# gsmwattsmonitor.net
KiCad netlist of a schematic drawn in EAGLE
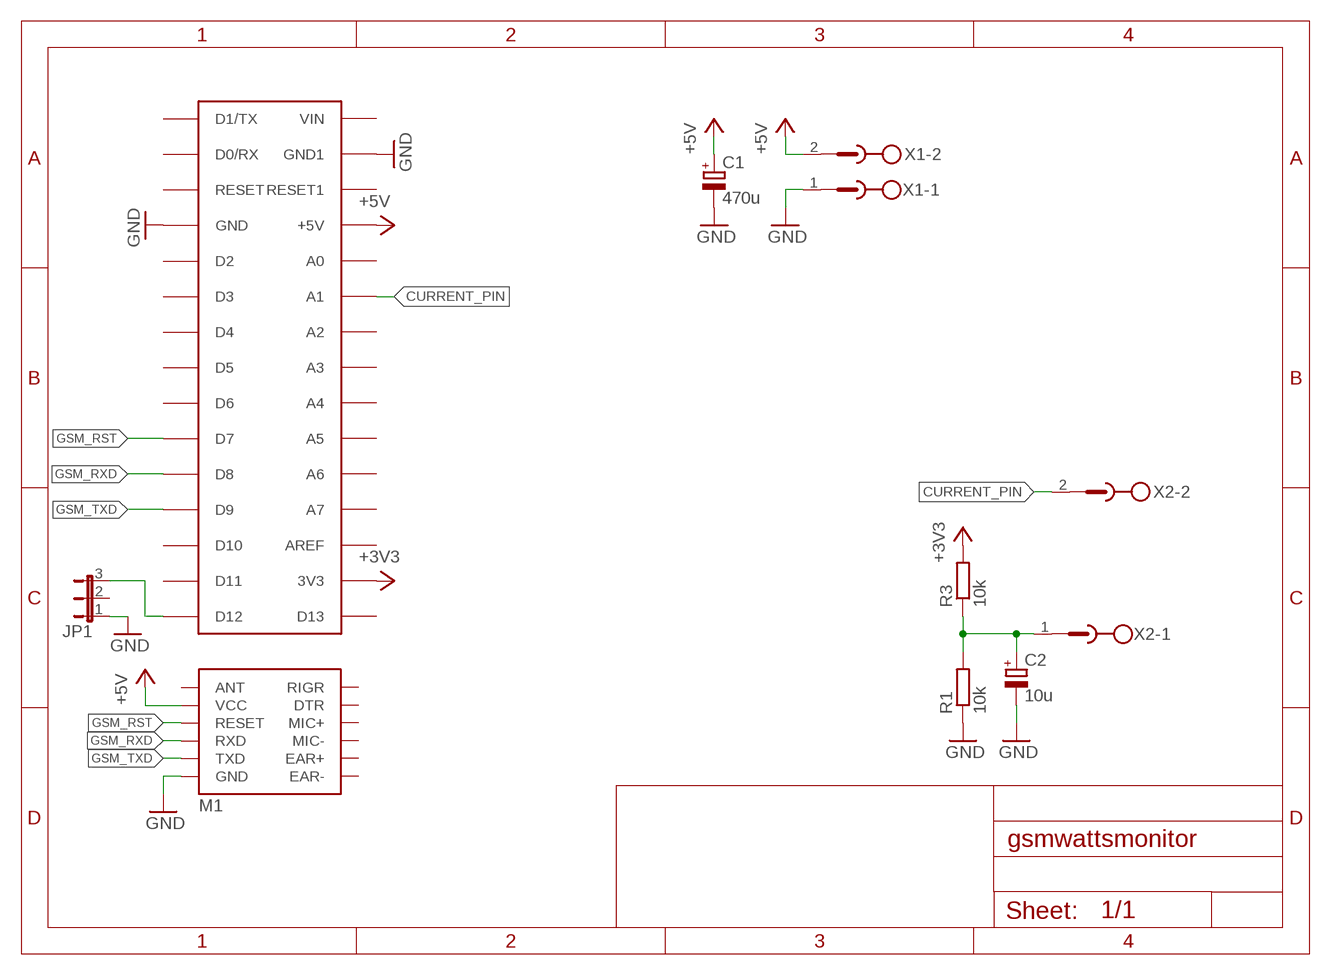
[diagram p0: schematic, sheet 1]

(export (version "E")
  (design (tool "Eeschema 10.0.6"))
  (components
    (comp (ref "C1")
      (value "470u")
      (footprint "eagle-import:E2,5-6")
      (libsource (lib "eagle-import") (part "CPOL-EUE2.5-6"))
    )
    (comp (ref "C2")
      (value "10u")
      (footprint "eagle-import:E2-4")
      (libsource (lib "eagle-import") (part "CPOL-EUE2-4"))
    )
    (comp (ref "JP1")
      (value "JP2E")
      (footprint "eagle-import:JP2")
      (libsource (lib "eagle-import") (part "JP2E"))
    )
    (comp (ref "M1")
      (value "SIM800L")
      (footprint "eagle-import:SIM800L")
      (libsource (lib "eagle-import") (part "SIM800L"))
    )
    (comp (ref "R1")
      (value "10k")
      (footprint "eagle-import:0204_7")
      (libsource (lib "eagle-import") (part "R-EU_0204/7"))
    )
    (comp (ref "R3")
      (value "10k")
      (footprint "eagle-import:0204_7")
      (libsource (lib "eagle-import") (part "R-EU_0204/7"))
    )
    (comp (ref "U$1")
      (value "ARDUINONANO")
      (footprint "eagle-import:PDIP-32")
      (libsource (lib "eagle-import") (part "ARDUINONANO"))
    )
    (comp (ref "X1")
      (value "MSTBV2")
      (footprint "eagle-import:MSTBV2")
      (libsource (lib "eagle-import") (part "MSTBV2"))
    )
    (comp (ref "X2")
      (value "MSTBV2")
      (footprint "eagle-import:MSTBV2")
      (libsource (lib "eagle-import") (part "MSTBV2"))
    )
  )
  (nets
    (net (code "1") (name "+3V3") (class "Default")
      (node (ref "R3") (pin "2") (pinfunction "2_2") (pintype "passive"))
      (node (ref "U$1") (pin "3V3") (pinfunction "3V3_3V3") (pintype "bidirectional"))
    )
    (net (code "2") (name "+5V") (class "Default")
      (node (ref "C1") (pin "+") (pinfunction "+_+") (pintype "passive"))
      (node (ref "M1") (pin "VCC") (pinfunction "VCC_VCC") (pintype "bidirectional"))
      (node (ref "U$1") (pin "+5V") (pinfunction "+5V_+5V") (pintype "bidirectional"))
      (node (ref "X1") (pin "2") (pinfunction "SK_2") (pintype "passive"))
    )
    (net (code "3") (name "CURRENT_PIN") (class "Default")
      (node (ref "U$1") (pin "A1") (pinfunction "A1_A1") (pintype "bidirectional"))
      (node (ref "X2") (pin "2") (pinfunction "SK_2") (pintype "passive"))
    )
    (net (code "4") (name "GND") (class "Default")
      (node (ref "C1") (pin "-") (pinfunction "-_-") (pintype "passive"))
      (node (ref "C2") (pin "-") (pinfunction "-_-") (pintype "passive"))
      (node (ref "JP1") (pin "1") (pinfunction "1_1") (pintype "passive"))
      (node (ref "M1") (pin "GND") (pinfunction "GND_GND") (pintype "bidirectional"))
      (node (ref "R1") (pin "1") (pinfunction "1_1") (pintype "passive"))
      (node (ref "U$1") (pin "GND") (pinfunction "GND_GND") (pintype "bidirectional"))
      (node (ref "U$1") (pin "GND1") (pinfunction "GND1_GND1") (pintype "bidirectional"))
      (node (ref "X1") (pin "1") (pinfunction "SK_1") (pintype "passive"))
    )
    (net (code "5") (name "GSM_RST") (class "Default")
      (node (ref "M1") (pin "RESET") (pinfunction "RESET_RESET") (pintype "bidirectional"))
      (node (ref "U$1") (pin "D7") (pinfunction "D7_D7") (pintype "bidirectional"))
    )
    (net (code "6") (name "GSM_RXD") (class "Default")
      (node (ref "M1") (pin "RXD") (pinfunction "RXD_RXD") (pintype "bidirectional"))
      (node (ref "U$1") (pin "D8") (pinfunction "D8_D8") (pintype "bidirectional"))
    )
    (net (code "7") (name "GSM_TXD") (class "Default")
      (node (ref "M1") (pin "TXD") (pinfunction "TXD_TXD") (pintype "bidirectional"))
      (node (ref "U$1") (pin "D9") (pinfunction "D9_D9") (pintype "bidirectional"))
    )
    (net (code "8") (name "Net-(JP1-Pad3)") (class "Default")
      (node (ref "JP1") (pin "3") (pinfunction "3_3") (pintype "passive"))
      (node (ref "U$1") (pin "D12") (pinfunction "D12_D12") (pintype "bidirectional"))
    )
    (net (code "9") (name "Net-(X2A-SK)") (class "Default")
      (node (ref "C2") (pin "+") (pinfunction "+_+") (pintype "passive"))
      (node (ref "R1") (pin "2") (pinfunction "2_2") (pintype "passive"))
      (node (ref "R3") (pin "1") (pinfunction "1_1") (pintype "passive"))
      (node (ref "X2") (pin "1") (pinfunction "SK_1") (pintype "passive"))
    )
    (net (code "10") (name "unconnected-(JP1-Pad2)") (class "Default")
      (node (ref "JP1") (pin "2") (pinfunction "2_2") (pintype "passive"))
    )
    (net (code "11") (name "unconnected-(M1-PadANT)") (class "Default")
      (node (ref "M1") (pin "ANT") (pinfunction "ANT_ANT") (pintype "bidirectional"))
    )
    (net (code "12") (name "unconnected-(M1-PadDTR)") (class "Default")
      (node (ref "M1") (pin "DTR") (pinfunction "DTR_DTR") (pintype "bidirectional"))
    )
    (net (code "13") (name "unconnected-(M1-PadEAR+)") (class "Default")
      (node (ref "M1") (pin "EAR+") (pinfunction "EAR+_EAR+") (pintype "bidirectional"))
    )
    (net (code "14") (name "unconnected-(M1-PadEAR-)") (class "Default")
      (node (ref "M1") (pin "EAR-") (pinfunction "EAR-_EAR-") (pintype "bidirectional"))
    )
    (net (code "15") (name "unconnected-(M1-PadMIC+)") (class "Default")
      (node (ref "M1") (pin "MIC+") (pinfunction "MIC+_MIC+") (pintype "bidirectional"))
    )
    (net (code "16") (name "unconnected-(M1-PadMIC-)") (class "Default")
      (node (ref "M1") (pin "MIC-") (pinfunction "MIC-_MIC-") (pintype "bidirectional"))
    )
    (net (code "17") (name "unconnected-(M1-PadRIGR)") (class "Default")
      (node (ref "M1") (pin "RIGR") (pinfunction "RIGR_RIGR") (pintype "bidirectional"))
    )
    (net (code "18") (name "unconnected-(U$1-PadA0)") (class "Default")
      (node (ref "U$1") (pin "A0") (pinfunction "A0_A0") (pintype "bidirectional"))
    )
    (net (code "19") (name "unconnected-(U$1-PadA2)") (class "Default")
      (node (ref "U$1") (pin "A2") (pinfunction "A2_A2") (pintype "bidirectional"))
    )
    (net (code "20") (name "unconnected-(U$1-PadA3)") (class "Default")
      (node (ref "U$1") (pin "A3") (pinfunction "A3_A3") (pintype "bidirectional"))
    )
    (net (code "21") (name "unconnected-(U$1-PadA4)") (class "Default")
      (node (ref "U$1") (pin "A4") (pinfunction "A4_A4") (pintype "bidirectional"))
    )
    (net (code "22") (name "unconnected-(U$1-PadA5)") (class "Default")
      (node (ref "U$1") (pin "A5") (pinfunction "A5_A5") (pintype "bidirectional"))
    )
    (net (code "23") (name "unconnected-(U$1-PadA6)") (class "Default")
      (node (ref "U$1") (pin "A6") (pinfunction "A6_A6") (pintype "bidirectional"))
    )
    (net (code "24") (name "unconnected-(U$1-PadA7)") (class "Default")
      (node (ref "U$1") (pin "A7") (pinfunction "A7_A7") (pintype "bidirectional"))
    )
    (net (code "25") (name "unconnected-(U$1-PadAREF)") (class "Default")
      (node (ref "U$1") (pin "AREF") (pinfunction "AREF_AREF") (pintype "bidirectional"))
    )
    (net (code "26") (name "unconnected-(U$1-PadD0{slash}RX)") (class "Default")
      (node (ref "U$1") (pin "D0/RX") (pinfunction "D0/RX_D0/RX") (pintype "bidirectional"))
    )
    (net (code "27") (name "unconnected-(U$1-PadD1{slash}TX)") (class "Default")
      (node (ref "U$1") (pin "D1/TX") (pinfunction "D1/TX_D1/TX") (pintype "bidirectional"))
    )
    (net (code "28") (name "unconnected-(U$1-PadD2)") (class "Default")
      (node (ref "U$1") (pin "D2") (pinfunction "D2_D2") (pintype "bidirectional"))
    )
    (net (code "29") (name "unconnected-(U$1-PadD3)") (class "Default")
      (node (ref "U$1") (pin "D3") (pinfunction "D3_D3") (pintype "bidirectional"))
    )
    (net (code "30") (name "unconnected-(U$1-PadD4)") (class "Default")
      (node (ref "U$1") (pin "D4") (pinfunction "D4_D4") (pintype "bidirectional"))
    )
    (net (code "31") (name "unconnected-(U$1-PadD5)") (class "Default")
      (node (ref "U$1") (pin "D5") (pinfunction "D5_D5") (pintype "bidirectional"))
    )
    (net (code "32") (name "unconnected-(U$1-PadD6)") (class "Default")
      (node (ref "U$1") (pin "D6") (pinfunction "D6_D6") (pintype "bidirectional"))
    )
    (net (code "33") (name "unconnected-(U$1-PadD10)") (class "Default")
      (node (ref "U$1") (pin "D10") (pinfunction "D10_D10") (pintype "bidirectional"))
    )
    (net (code "34") (name "unconnected-(U$1-PadD11)") (class "Default")
      (node (ref "U$1") (pin "D11") (pinfunction "D11_D11") (pintype "bidirectional"))
    )
    (net (code "35") (name "unconnected-(U$1-PadD13)") (class "Default")
      (node (ref "U$1") (pin "D13") (pinfunction "D13_D13") (pintype "bidirectional"))
    )
    (net (code "36") (name "unconnected-(U$1-PadRESET)") (class "Default")
      (node (ref "U$1") (pin "RESET") (pinfunction "RESET_RESET") (pintype "bidirectional"))
    )
    (net (code "37") (name "unconnected-(U$1-PadRESET1)") (class "Default")
      (node (ref "U$1") (pin "RESET1") (pinfunction "RESET1_RESET1") (pintype "bidirectional"))
    )
    (net (code "38") (name "unconnected-(U$1-PadVIN)") (class "Default")
      (node (ref "U$1") (pin "VIN") (pinfunction "VIN_VIN") (pintype "bidirectional"))
    )
  )
)
